# mcprog.net
KiCad netlist of a schematic drawn in EAGLE
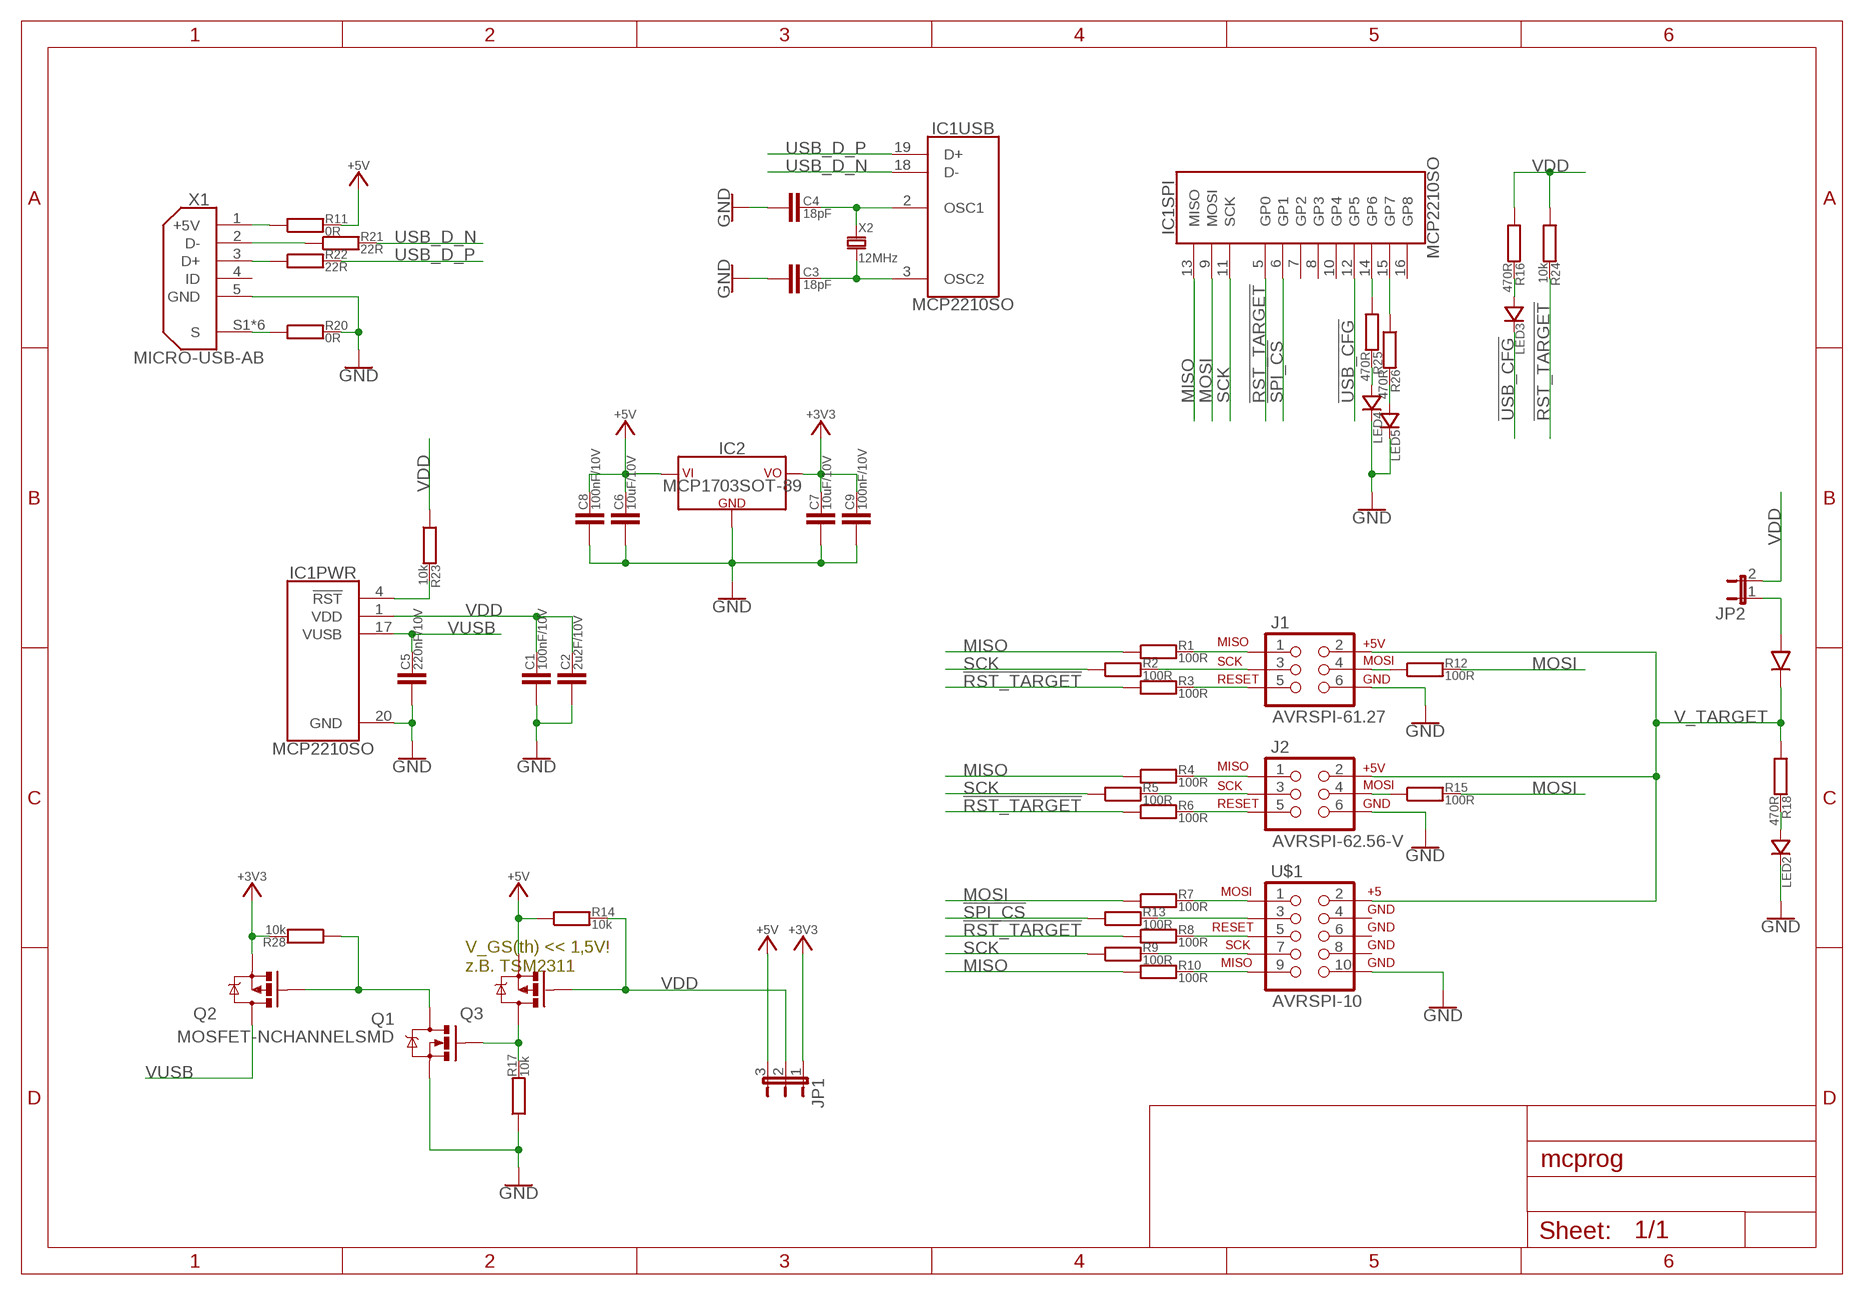
[diagram p0: schematic, sheet 1]

(export (version "E")
  (design (tool "Eeschema 10.0.6"))
  (components
    (comp (ref "C1")
      (value "100nF/10V")
      (footprint "eagle-import:C0603")
      (libsource (lib "eagle-import") (part "C0603"))
    )
    (comp (ref "C2")
      (value "2u2F/10V")
      (footprint "eagle-import:C1206")
      (libsource (lib "eagle-import") (part "C1206"))
    )
    (comp (ref "C3")
      (value "18pF")
      (footprint "eagle-import:C0603")
      (libsource (lib "eagle-import") (part "C0603"))
    )
    (comp (ref "C4")
      (value "18pF")
      (footprint "eagle-import:C0603")
      (libsource (lib "eagle-import") (part "C0603"))
    )
    (comp (ref "C5")
      (value "220nF/10V")
      (footprint "eagle-import:C0603")
      (libsource (lib "eagle-import") (part "C0603"))
    )
    (comp (ref "C6")
      (value "10uF/10V")
      (footprint "eagle-import:C1206")
      (libsource (lib "eagle-import") (part "C1206"))
    )
    (comp (ref "C7")
      (value "10uF/10V")
      (footprint "eagle-import:C1206")
      (libsource (lib "eagle-import") (part "C1206"))
    )
    (comp (ref "C8")
      (value "100nF/10V")
      (footprint "eagle-import:C0603")
      (libsource (lib "eagle-import") (part "C0603"))
    )
    (comp (ref "C9")
      (value "100nF/10V")
      (footprint "eagle-import:C0603")
      (libsource (lib "eagle-import") (part "C0603"))
    )
    (comp (ref "D1")
      (value "1N5819HW")
      (footprint "eagle-import:SOD123")
      (fields (field (name "MF") "DIODES INC.") (field (name "MPN") "1N5819HW-7-F"))
      (libsource (lib "eagle-import") (part "1N5819HW"))
    )
    (comp (ref "IC1")
      (value "MCP2210SO")
      (footprint "eagle-import:SOIC20-W")
      (libsource (lib "eagle-import") (part "MCP2210SO"))
    )
    (comp (ref "IC2")
      (value "MCP1703SOT-89")
      (footprint "eagle-import:SOT89")
      (libsource (lib "eagle-import") (part "MCP1703SOT-89"))
    )
    (comp (ref "J1")
      (value "AVRSPI-61.27")
      (footprint "eagle-import:2X3-1.27")
      (libsource (lib "eagle-import") (part "AVRSPI-61.27"))
    )
    (comp (ref "J2")
      (value "AVRSPI-62.56-V")
      (footprint "eagle-import:2X3-NS")
      (libsource (lib "eagle-import") (part "AVRSPI-62.56-V"))
    )
    (comp (ref "JP1")
      (value "JP2E")
      (footprint "eagle-import:JP2")
      (libsource (lib "eagle-import") (part "JP2E"))
    )
    (comp (ref "JP2")
      (value "JP1E")
      (footprint "eagle-import:JP1")
      (libsource (lib "eagle-import") (part "JP1E"))
    )
    (comp (ref "LED2")
      (value "LED0603")
      (footprint "eagle-import:LED0603")
      (libsource (lib "eagle-import") (part "LED0603"))
    )
    (comp (ref "LED3")
      (value "LED0603")
      (footprint "eagle-import:LED0603")
      (libsource (lib "eagle-import") (part "LED0603"))
    )
    (comp (ref "LED4")
      (value "LED0603")
      (footprint "eagle-import:LED0603")
      (libsource (lib "eagle-import") (part "LED0603"))
    )
    (comp (ref "LED5")
      (value "LED0603")
      (footprint "eagle-import:LED0603")
      (libsource (lib "eagle-import") (part "LED0603"))
    )
    (comp (ref "Q1")
      (value "MOSFET-NCHANNELSMD")
      (footprint "eagle-import:SOT23-3")
      (libsource (lib "eagle-import") (part "MOSFET-NCHANNELSMD"))
    )
    (comp (ref "Q2")
      (value "MOSFET-PCHANNEL")
      (footprint "eagle-import:SOT23")
      (libsource (lib "eagle-import") (part "MOSFET-PCHANNEL"))
    )
    (comp (ref "Q3")
      (value "MOSFET-PCHANNEL")
      (footprint "eagle-import:SOT23")
      (libsource (lib "eagle-import") (part "MOSFET-PCHANNEL"))
    )
    (comp (ref "R1")
      (value "100R")
      (footprint "eagle-import:R0603")
      (libsource (lib "eagle-import") (part "R0603"))
    )
    (comp (ref "R2")
      (value "100R")
      (footprint "eagle-import:R0603")
      (libsource (lib "eagle-import") (part "R0603"))
    )
    (comp (ref "R3")
      (value "100R")
      (footprint "eagle-import:R0603")
      (libsource (lib "eagle-import") (part "R0603"))
    )
    (comp (ref "R4")
      (value "100R")
      (footprint "eagle-import:R0603")
      (libsource (lib "eagle-import") (part "R0603"))
    )
    (comp (ref "R5")
      (value "100R")
      (footprint "eagle-import:R0603")
      (libsource (lib "eagle-import") (part "R0603"))
    )
    (comp (ref "R6")
      (value "100R")
      (footprint "eagle-import:R0603")
      (libsource (lib "eagle-import") (part "R0603"))
    )
    (comp (ref "R7")
      (value "100R")
      (footprint "eagle-import:R0603")
      (libsource (lib "eagle-import") (part "R0603"))
    )
    (comp (ref "R8")
      (value "100R")
      (footprint "eagle-import:R0603")
      (libsource (lib "eagle-import") (part "R0603"))
    )
    (comp (ref "R9")
      (value "100R")
      (footprint "eagle-import:R0603")
      (libsource (lib "eagle-import") (part "R0603"))
    )
    (comp (ref "R10")
      (value "100R")
      (footprint "eagle-import:R0603")
      (libsource (lib "eagle-import") (part "R0603"))
    )
    (comp (ref "R11")
      (value "0R")
      (footprint "eagle-import:R0603")
      (libsource (lib "eagle-import") (part "R0603"))
    )
    (comp (ref "R12")
      (value "100R")
      (footprint "eagle-import:R0603")
      (libsource (lib "eagle-import") (part "R0603"))
    )
    (comp (ref "R13")
      (value "100R")
      (footprint "eagle-import:R0603")
      (libsource (lib "eagle-import") (part "R0603"))
    )
    (comp (ref "R14")
      (value "10k")
      (footprint "eagle-import:R0603")
      (libsource (lib "eagle-import") (part "R0603"))
    )
    (comp (ref "R15")
      (value "100R")
      (footprint "eagle-import:R0603")
      (libsource (lib "eagle-import") (part "R0603"))
    )
    (comp (ref "R16")
      (value "470R")
      (footprint "eagle-import:R0603")
      (libsource (lib "eagle-import") (part "R0603"))
    )
    (comp (ref "R17")
      (value "10k")
      (footprint "eagle-import:R0603")
      (libsource (lib "eagle-import") (part "R0603"))
    )
    (comp (ref "R18")
      (value "470R")
      (footprint "eagle-import:R0603")
      (libsource (lib "eagle-import") (part "R0603"))
    )
    (comp (ref "R20")
      (value "0R")
      (footprint "eagle-import:R0603")
      (libsource (lib "eagle-import") (part "R0603"))
    )
    (comp (ref "R21")
      (value "22R")
      (footprint "eagle-import:R0603")
      (libsource (lib "eagle-import") (part "R0603"))
    )
    (comp (ref "R22")
      (value "22R")
      (footprint "eagle-import:R0603")
      (libsource (lib "eagle-import") (part "R0603"))
    )
    (comp (ref "R23")
      (value "10k")
      (footprint "eagle-import:R0603")
      (libsource (lib "eagle-import") (part "R0603"))
    )
    (comp (ref "R24")
      (value "10k")
      (footprint "eagle-import:R0603")
      (libsource (lib "eagle-import") (part "R0603"))
    )
    (comp (ref "R25")
      (value "470R")
      (footprint "eagle-import:R0603")
      (libsource (lib "eagle-import") (part "R0603"))
    )
    (comp (ref "R26")
      (value "470R")
      (footprint "eagle-import:R0603")
      (libsource (lib "eagle-import") (part "R0603"))
    )
    (comp (ref "R28")
      (value "10k")
      (footprint "eagle-import:R0603")
      (libsource (lib "eagle-import") (part "R0603"))
    )
    (comp (ref "U$1")
      (value "AVRSPI-10")
      (footprint "eagle-import:AVR_ICSP")
      (libsource (lib "eagle-import") (part "AVRSPI-10"))
    )
    (comp (ref "X1")
      (value "MICRO-USB-AB")
      (footprint "eagle-import:ZX62-B-5PA(11)")
      (fields (field (name "MF") "HIROSE") (field (name "MPN") "ZX62-AB-5PA(11)"))
      (libsource (lib "eagle-import") (part "MICRO-USB-AB"))
    )
    (comp (ref "X2")
      (value "12MHz")
      (footprint "eagle-import:HC49UP")
      (libsource (lib "eagle-import") (part "CRYSTALHC49UP"))
    )
  )
  (nets
    (net (code "1") (name "+3V3") (class "Default")
      (node (ref "C7") (pin "2") (pinfunction "2_2") (pintype "passive"))
      (node (ref "C9") (pin "2") (pinfunction "2_2") (pintype "passive"))
      (node (ref "IC2") (pin "3") (pinfunction "VCC_3") (pintype "power_in"))
      (node (ref "JP1") (pin "1") (pinfunction "1_1") (pintype "passive"))
      (node (ref "Q2") (pin "2") (pinfunction "S_2") (pintype "passive"))
      (node (ref "R28") (pin "2") (pinfunction "2_2") (pintype "passive"))
    )
    (net (code "2") (name "+5V") (class "Default")
      (node (ref "C6") (pin "2") (pinfunction "2_2") (pintype "passive"))
      (node (ref "C8") (pin "2") (pinfunction "2_2") (pintype "passive"))
      (node (ref "IC2") (pin "2") (pinfunction "VIN_2") (pintype "power_in"))
      (node (ref "IC2") (pin "4") (pinfunction "VIN_4") (pintype "power_in"))
      (node (ref "JP1") (pin "3") (pinfunction "3_3") (pintype "passive"))
      (node (ref "Q3") (pin "2") (pinfunction "S_2") (pintype "passive"))
      (node (ref "R11") (pin "2") (pinfunction "2_2") (pintype "passive"))
      (node (ref "R14") (pin "1") (pinfunction "1_1") (pintype "passive"))
    )
    (net (code "3") (name "/MISO") (class "Default")
      (node (ref "IC1") (pin "13") (pinfunction "MISO_13") (pintype "input"))
      (node (ref "R1") (pin "1") (pinfunction "1_1") (pintype "passive"))
      (node (ref "R10") (pin "1") (pinfunction "1_1") (pintype "passive"))
      (node (ref "R4") (pin "1") (pinfunction "1_1") (pintype "passive"))
    )
    (net (code "4") (name "/MOSI") (class "Default")
      (node (ref "IC1") (pin "9") (pinfunction "MOSI_9") (pintype "output"))
      (node (ref "R12") (pin "2") (pinfunction "2_2") (pintype "passive"))
      (node (ref "R15") (pin "2") (pinfunction "2_2") (pintype "passive"))
      (node (ref "R7") (pin "1") (pinfunction "1_1") (pintype "passive"))
    )
    (net (code "5") (name "/SCK") (class "Default")
      (node (ref "IC1") (pin "11") (pinfunction "SCK_11") (pintype "output"))
      (node (ref "R2") (pin "1") (pinfunction "1_1") (pintype "passive"))
      (node (ref "R5") (pin "1") (pinfunction "1_1") (pintype "passive"))
      (node (ref "R9") (pin "1") (pinfunction "1_1") (pintype "passive"))
    )
    (net (code "6") (name "/USB_D_N") (class "Default")
      (node (ref "IC1") (pin "18") (pinfunction "D-_18") (pintype "passive"))
      (node (ref "R21") (pin "2") (pinfunction "2_2") (pintype "passive"))
    )
    (net (code "7") (name "/USB_D_P") (class "Default")
      (node (ref "IC1") (pin "19") (pinfunction "D+_19") (pintype "passive"))
      (node (ref "R22") (pin "2") (pinfunction "2_2") (pintype "passive"))
    )
    (net (code "8") (name "/VDD") (class "Default")
      (node (ref "C1") (pin "2") (pinfunction "2_2") (pintype "passive"))
      (node (ref "C2") (pin "2") (pinfunction "2_2") (pintype "passive"))
      (node (ref "IC1") (pin "1") (pinfunction "VDD_1") (pintype "power_in"))
      (node (ref "JP1") (pin "2") (pinfunction "2_2") (pintype "passive"))
      (node (ref "JP2") (pin "2") (pinfunction "2_2") (pintype "passive"))
      (node (ref "Q3") (pin "1") (pinfunction "G_1") (pintype "passive"))
      (node (ref "R14") (pin "2") (pinfunction "2_2") (pintype "passive"))
      (node (ref "R16") (pin "1") (pinfunction "1_1") (pintype "passive"))
      (node (ref "R23") (pin "1") (pinfunction "1_1") (pintype "passive"))
      (node (ref "R24") (pin "1") (pinfunction "1_1") (pintype "passive"))
    )
    (net (code "9") (name "/VUSB") (class "Default")
      (node (ref "C5") (pin "2") (pinfunction "2_2") (pintype "passive"))
      (node (ref "IC1") (pin "17") (pinfunction "VUSB_17") (pintype "power_in"))
      (node (ref "Q2") (pin "3") (pinfunction "D_3") (pintype "passive"))
    )
    (net (code "10") (name "/V_TARGET") (class "Default")
      (node (ref "D1") (pin "C") (pinfunction "C_C") (pintype "passive"))
      (node (ref "J1") (pin "2") (pinfunction "+5V_2") (pintype "passive"))
      (node (ref "J2") (pin "2") (pinfunction "+5V_2") (pintype "passive"))
      (node (ref "R18") (pin "1") (pinfunction "1_1") (pintype "passive"))
      (node (ref "U$1") (pin "2") (pinfunction "2_2") (pintype "passive"))
    )
    (net (code "11") (name "/~{RST_TARGET}") (class "Default")
      (node (ref "IC1") (pin "5") (pinfunction "GP0_5") (pintype "bidirectional"))
      (node (ref "R24") (pin "2") (pinfunction "2_2") (pintype "passive"))
      (node (ref "R3") (pin "1") (pinfunction "1_1") (pintype "passive"))
      (node (ref "R6") (pin "1") (pinfunction "1_1") (pintype "passive"))
      (node (ref "R8") (pin "1") (pinfunction "1_1") (pintype "passive"))
    )
    (net (code "12") (name "/~{SPI_CS}") (class "Default")
      (node (ref "IC1") (pin "6") (pinfunction "GP1_6") (pintype "bidirectional"))
      (node (ref "R13") (pin "1") (pinfunction "1_1") (pintype "passive"))
    )
    (net (code "13") (name "/~{USB_CFG}") (class "Default")
      (node (ref "IC1") (pin "12") (pinfunction "GP5_12") (pintype "bidirectional"))
      (node (ref "LED3") (pin "C") (pinfunction "C_C") (pintype "passive"))
    )
    (net (code "14") (name "GND") (class "Default")
      (node (ref "C1") (pin "1") (pinfunction "1_1") (pintype "passive"))
      (node (ref "C2") (pin "1") (pinfunction "1_1") (pintype "passive"))
      (node (ref "C3") (pin "1") (pinfunction "1_1") (pintype "passive"))
      (node (ref "C4") (pin "1") (pinfunction "1_1") (pintype "passive"))
      (node (ref "C5") (pin "1") (pinfunction "1_1") (pintype "passive"))
      (node (ref "C6") (pin "1") (pinfunction "1_1") (pintype "passive"))
      (node (ref "C7") (pin "1") (pinfunction "1_1") (pintype "passive"))
      (node (ref "C8") (pin "1") (pinfunction "1_1") (pintype "passive"))
      (node (ref "C9") (pin "1") (pinfunction "1_1") (pintype "passive"))
      (node (ref "IC1") (pin "20") (pinfunction "GND_20") (pintype "power_in"))
      (node (ref "IC2") (pin "1") (pinfunction "GND_1") (pintype "power_in"))
      (node (ref "J1") (pin "6") (pinfunction "GND_6") (pintype "passive"))
      (node (ref "J2") (pin "6") (pinfunction "GND_6") (pintype "passive"))
      (node (ref "LED2") (pin "C") (pinfunction "C_C") (pintype "passive"))
      (node (ref "LED4") (pin "C") (pinfunction "C_C") (pintype "passive"))
      (node (ref "LED5") (pin "C") (pinfunction "C_C") (pintype "passive"))
      (node (ref "Q1") (pin "2") (pinfunction "S_2") (pintype "passive"))
      (node (ref "R17") (pin "1") (pinfunction "1_1") (pintype "passive"))
      (node (ref "R20") (pin "2") (pinfunction "2_2") (pintype "passive"))
      (node (ref "U$1") (pin "10") (pinfunction "10_10") (pintype "passive"))
      (node (ref "X1") (pin "5") (pinfunction "GND_5") (pintype "passive"))
    )
    (net (code "15") (name "Net-(D1-PadA)") (class "Default")
      (node (ref "D1") (pin "A") (pinfunction "A_A") (pintype "passive"))
      (node (ref "JP2") (pin "1") (pinfunction "1_1") (pintype "passive"))
    )
    (net (code "16") (name "Net-(IC1A-~{RST})") (class "Default")
      (node (ref "IC1") (pin "4") (pinfunction "~{RST}_4") (pintype "input"))
      (node (ref "R23") (pin "2") (pinfunction "2_2") (pintype "passive"))
    )
    (net (code "17") (name "Net-(IC1B-GP6)") (class "Default")
      (node (ref "IC1") (pin "14") (pinfunction "GP6_14") (pintype "bidirectional"))
      (node (ref "R25") (pin "1") (pinfunction "1_1") (pintype "passive"))
    )
    (net (code "18") (name "Net-(IC1B-GP7)") (class "Default")
      (node (ref "IC1") (pin "15") (pinfunction "GP7_15") (pintype "bidirectional"))
      (node (ref "R26") (pin "1") (pinfunction "1_1") (pintype "passive"))
    )
    (net (code "19") (name "Net-(IC1C-OSC1)") (class "Default")
      (node (ref "C4") (pin "2") (pinfunction "2_2") (pintype "passive"))
      (node (ref "IC1") (pin "2") (pinfunction "OSC1_2") (pintype "passive"))
      (node (ref "X2") (pin "1") (pinfunction "1_1") (pintype "passive"))
    )
    (net (code "20") (name "Net-(IC1C-OSC2)") (class "Default")
      (node (ref "C3") (pin "2") (pinfunction "2_2") (pintype "passive"))
      (node (ref "IC1") (pin "3") (pinfunction "OSC2_3") (pintype "passive"))
      (node (ref "X2") (pin "2") (pinfunction "2_2") (pintype "passive"))
    )
    (net (code "21") (name "Net-(J1-MISO)") (class "Default")
      (node (ref "J1") (pin "1") (pinfunction "MISO_1") (pintype "passive"))
      (node (ref "R1") (pin "2") (pinfunction "2_2") (pintype "passive"))
    )
    (net (code "22") (name "Net-(J1-MOSI)") (class "Default")
      (node (ref "J1") (pin "4") (pinfunction "MOSI_4") (pintype "passive"))
      (node (ref "R12") (pin "1") (pinfunction "1_1") (pintype "passive"))
    )
    (net (code "23") (name "Net-(J1-RESET)") (class "Default")
      (node (ref "J1") (pin "5") (pinfunction "RESET_5") (pintype "passive"))
      (node (ref "R3") (pin "2") (pinfunction "2_2") (pintype "passive"))
    )
    (net (code "24") (name "Net-(J1-SCK)") (class "Default")
      (node (ref "J1") (pin "3") (pinfunction "SCK_3") (pintype "passive"))
      (node (ref "R2") (pin "2") (pinfunction "2_2") (pintype "passive"))
    )
    (net (code "25") (name "Net-(J2-MISO)") (class "Default")
      (node (ref "J2") (pin "1") (pinfunction "MISO_1") (pintype "passive"))
      (node (ref "R4") (pin "2") (pinfunction "2_2") (pintype "passive"))
    )
    (net (code "26") (name "Net-(J2-MOSI)") (class "Default")
      (node (ref "J2") (pin "4") (pinfunction "MOSI_4") (pintype "passive"))
      (node (ref "R15") (pin "1") (pinfunction "1_1") (pintype "passive"))
    )
    (net (code "27") (name "Net-(J2-RESET)") (class "Default")
      (node (ref "J2") (pin "5") (pinfunction "RESET_5") (pintype "passive"))
      (node (ref "R6") (pin "2") (pinfunction "2_2") (pintype "passive"))
    )
    (net (code "28") (name "Net-(J2-SCK)") (class "Default")
      (node (ref "J2") (pin "3") (pinfunction "SCK_3") (pintype "passive"))
      (node (ref "R5") (pin "2") (pinfunction "2_2") (pintype "passive"))
    )
    (net (code "29") (name "Net-(LED2-PadA)") (class "Default")
      (node (ref "LED2") (pin "A") (pinfunction "A_A") (pintype "passive"))
      (node (ref "R18") (pin "2") (pinfunction "2_2") (pintype "passive"))
    )
    (net (code "30") (name "Net-(LED3-PadA)") (class "Default")
      (node (ref "LED3") (pin "A") (pinfunction "A_A") (pintype "passive"))
      (node (ref "R16") (pin "2") (pinfunction "2_2") (pintype "passive"))
    )
    (net (code "31") (name "Net-(LED4-PadA)") (class "Default")
      (node (ref "LED4") (pin "A") (pinfunction "A_A") (pintype "passive"))
      (node (ref "R25") (pin "2") (pinfunction "2_2") (pintype "passive"))
    )
    (net (code "32") (name "Net-(LED5-PadA)") (class "Default")
      (node (ref "LED5") (pin "A") (pinfunction "A_A") (pintype "passive"))
      (node (ref "R26") (pin "2") (pinfunction "2_2") (pintype "passive"))
    )
    (net (code "33") (name "Net-(Q1-D)") (class "Default")
      (node (ref "Q1") (pin "3") (pinfunction "D_3") (pintype "passive"))
      (node (ref "Q2") (pin "1") (pinfunction "G_1") (pintype "passive"))
      (node (ref "R28") (pin "1") (pinfunction "1_1") (pintype "passive"))
    )
    (net (code "34") (name "Net-(Q1-G)") (class "Default")
      (node (ref "Q1") (pin "1") (pinfunction "G_1") (pintype "passive"))
      (node (ref "Q3") (pin "3") (pinfunction "D_3") (pintype "passive"))
      (node (ref "R17") (pin "2") (pinfunction "2_2") (pintype "passive"))
    )
    (net (code "35") (name "Net-(R7-Pad2)") (class "Default")
      (node (ref "R7") (pin "2") (pinfunction "2_2") (pintype "passive"))
      (node (ref "U$1") (pin "1") (pinfunction "1_1") (pintype "passive"))
    )
    (net (code "36") (name "Net-(R8-Pad2)") (class "Default")
      (node (ref "R8") (pin "2") (pinfunction "2_2") (pintype "passive"))
      (node (ref "U$1") (pin "5") (pinfunction "5_5") (pintype "passive"))
    )
    (net (code "37") (name "Net-(R9-Pad2)") (class "Default")
      (node (ref "R9") (pin "2") (pinfunction "2_2") (pintype "passive"))
      (node (ref "U$1") (pin "7") (pinfunction "7_7") (pintype "passive"))
    )
    (net (code "38") (name "Net-(R10-Pad2)") (class "Default")
      (node (ref "R10") (pin "2") (pinfunction "2_2") (pintype "passive"))
      (node (ref "U$1") (pin "9") (pinfunction "9_9") (pintype "passive"))
    )
    (net (code "39") (name "Net-(R13-Pad2)") (class "Default")
      (node (ref "R13") (pin "2") (pinfunction "2_2") (pintype "passive"))
      (node (ref "U$1") (pin "3") (pinfunction "3_3") (pintype "passive"))
    )
    (net (code "40") (name "Net-(R20-Pad1)") (class "Default")
      (node (ref "R20") (pin "1") (pinfunction "1_1") (pintype "passive"))
      (node (ref "X1") (pin "S1") (pinfunction "S_S1") (pintype "passive"))
      (node (ref "X1") (pin "S2") (pinfunction "S_S2") (pintype "passive"))
      (node (ref "X1") (pin "S3") (pinfunction "S_S3") (pintype "passive"))
      (node (ref "X1") (pin "S4") (pinfunction "S_S4") (pintype "passive"))
      (node (ref "X1") (pin "S5") (pinfunction "S_S5") (pintype "passive"))
      (node (ref "X1") (pin "S6") (pinfunction "S_S6") (pintype "passive"))
    )
    (net (code "41") (name "Net-(X1-+5V)") (class "Default")
      (node (ref "R11") (pin "1") (pinfunction "1_1") (pintype "passive"))
      (node (ref "X1") (pin "1") (pinfunction "+5V_1") (pintype "passive"))
    )
    (net (code "42") (name "Net-(X1-D+)") (class "Default")
      (node (ref "R22") (pin "1") (pinfunction "1_1") (pintype "passive"))
      (node (ref "X1") (pin "3") (pinfunction "D+_3") (pintype "passive"))
    )
    (net (code "43") (name "Net-(X1-D-)") (class "Default")
      (node (ref "R21") (pin "1") (pinfunction "1_1") (pintype "passive"))
      (node (ref "X1") (pin "2") (pinfunction "D-_2") (pintype "passive"))
    )
    (net (code "44") (name "unconnected-(IC1B-GP2-Pad7)") (class "Default")
      (node (ref "IC1") (pin "7") (pinfunction "GP2_7") (pintype "bidirectional"))
    )
    (net (code "45") (name "unconnected-(IC1B-GP3-Pad8)") (class "Default")
      (node (ref "IC1") (pin "8") (pinfunction "GP3_8") (pintype "bidirectional"))
    )
    (net (code "46") (name "unconnected-(IC1B-GP4-Pad10)") (class "Default")
      (node (ref "IC1") (pin "10") (pinfunction "GP4_10") (pintype "bidirectional"))
    )
    (net (code "47") (name "unconnected-(IC1B-GP8-Pad16)") (class "Default")
      (node (ref "IC1") (pin "16") (pinfunction "GP8_16") (pintype "bidirectional"))
    )
    (net (code "48") (name "unconnected-(U$1-Pad4)") (class "Default")
      (node (ref "U$1") (pin "4") (pinfunction "4_4") (pintype "passive"))
    )
    (net (code "49") (name "unconnected-(U$1-Pad6)") (class "Default")
      (node (ref "U$1") (pin "6") (pinfunction "6_6") (pintype "passive"))
    )
    (net (code "50") (name "unconnected-(U$1-Pad8)") (class "Default")
      (node (ref "U$1") (pin "8") (pinfunction "8_8") (pintype "passive"))
    )
    (net (code "51") (name "unconnected-(X1-ID-Pad4)") (class "Default")
      (node (ref "X1") (pin "4") (pinfunction "ID_4") (pintype "passive"))
    )
  )
)
